# Active_comm_control_1_0.net
KiCad netlist of a schematic drawn in EAGLE
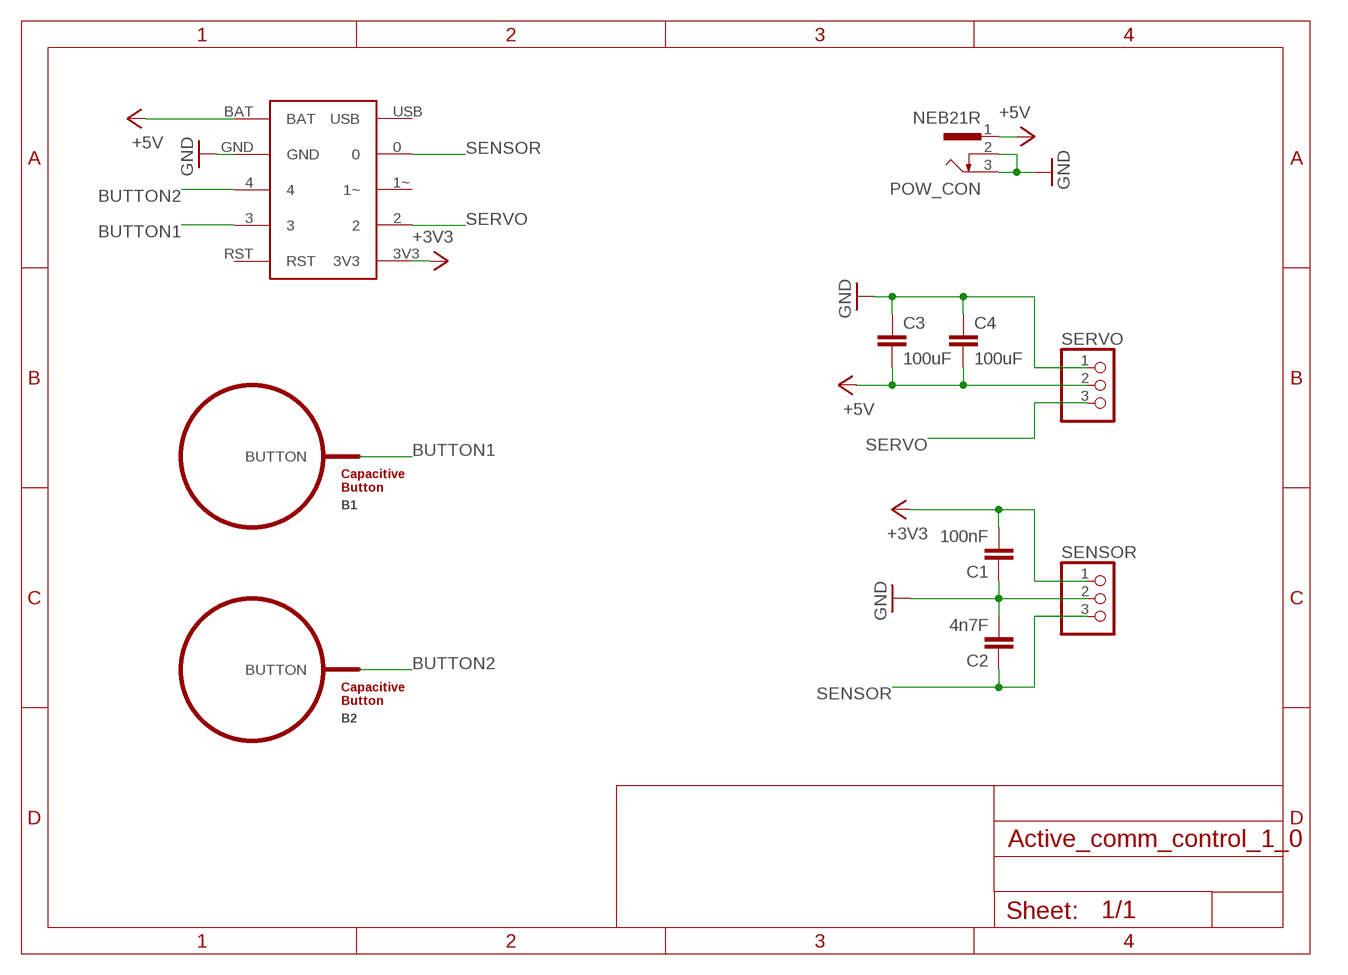
[diagram p0: schematic, sheet 1]

(export (version "E")
  (design (tool "Eeschema 10.0.6"))
  (components
    (comp (ref "B1")
      (value "BUTTON_PASSIVE10MM")
      (footprint "eagle-import:BUTTON_PASSIVE_10MM")
      (libsource (lib "eagle-import") (part "BUTTON_PASSIVE10MM"))
    )
    (comp (ref "B2")
      (value "BUTTON_PASSIVE10MM")
      (footprint "eagle-import:BUTTON_PASSIVE_10MM")
      (libsource (lib "eagle-import") (part "BUTTON_PASSIVE10MM"))
    )
    (comp (ref "C1")
      (value "100nF")
      (footprint "eagle-import:C0805")
      (libsource (lib "eagle-import") (part "resistor_C-EUC0805"))
    )
    (comp (ref "C2")
      (value "4n7F")
      (footprint "eagle-import:C0805")
      (libsource (lib "eagle-import") (part "resistor_C-EUC0805"))
    )
    (comp (ref "C3")
      (value "100uF")
      (footprint "eagle-import:C1206")
      (libsource (lib "eagle-import") (part "C-EUC1206"))
    )
    (comp (ref "C4")
      (value "100uF")
      (footprint "eagle-import:C1206")
      (libsource (lib "eagle-import") (part "C-EUC1206"))
    )
    (comp (ref "POW_CON")
      (value "NEB21R")
      (footprint "eagle-import:NEB21R")
      (fields (field (name "MPN") "NEB 21 R"))
      (libsource (lib "eagle-import") (part "NEB21R"))
    )
    (comp (ref "SENSOR")
      (value "PINHD-1X3")
      (footprint "eagle-import:1X03")
      (libsource (lib "eagle-import") (part "PINHD-1X3"))
    )
    (comp (ref "SERVO")
      (value "PINHD-1X3")
      (footprint "eagle-import:1X03")
      (libsource (lib "eagle-import") (part "PINHD-1X3"))
    )
    (comp (ref "TRINKET-M0")
      (value "TRINKET-M0")
      (footprint "eagle-import:TRINKET-M0-NO-HOLES")
      (libsource (lib "eagle-import") (part "TRINKET-M0"))
    )
  )
  (nets
    (net (code "1") (name "+3V3") (class "Default")
      (node (ref "C1") (pin "2") (pinfunction "2_2") (pintype "passive"))
      (node (ref "SENSOR") (pin "1") (pinfunction "1_1") (pintype "passive"))
      (node (ref "TRINKET-M0") (pin "3V3") (pinfunction "3V3_3V3") (pintype "bidirectional"))
    )
    (net (code "2") (name "+5V") (class "Default")
      (node (ref "C3") (pin "2") (pinfunction "2_2") (pintype "passive"))
      (node (ref "C4") (pin "2") (pinfunction "2_2") (pintype "passive"))
      (node (ref "POW_CON") (pin "1") (pinfunction "1_1") (pintype "passive"))
      (node (ref "SERVO") (pin "2") (pinfunction "2_2") (pintype "passive"))
      (node (ref "TRINKET-M0") (pin "BAT") (pinfunction "BAT_BAT") (pintype "bidirectional"))
    )
    (net (code "3") (name "/BUTTON1") (class "Default")
      (node (ref "B1") (pin "BUTTON") (pinfunction "BUTTON_BUTTON") (pintype "passive"))
      (node (ref "TRINKET-M0") (pin "3") (pinfunction "3_3") (pintype "bidirectional"))
    )
    (net (code "4") (name "/BUTTON2") (class "Default")
      (node (ref "B2") (pin "BUTTON") (pinfunction "BUTTON_BUTTON") (pintype "passive"))
      (node (ref "TRINKET-M0") (pin "4") (pinfunction "4_4") (pintype "bidirectional"))
    )
    (net (code "5") (name "/SENSOR") (class "Default")
      (node (ref "C2") (pin "1") (pinfunction "1_1") (pintype "passive"))
      (node (ref "SENSOR") (pin "3") (pinfunction "3_3") (pintype "passive"))
      (node (ref "TRINKET-M0") (pin "0") (pinfunction "0_0") (pintype "bidirectional"))
    )
    (net (code "6") (name "/SERVO") (class "Default")
      (node (ref "SERVO") (pin "3") (pinfunction "3_3") (pintype "passive"))
      (node (ref "TRINKET-M0") (pin "2") (pinfunction "2_2") (pintype "bidirectional"))
    )
    (net (code "7") (name "GND") (class "Default")
      (node (ref "C1") (pin "1") (pinfunction "1_1") (pintype "passive"))
      (node (ref "C2") (pin "2") (pinfunction "2_2") (pintype "passive"))
      (node (ref "C3") (pin "1") (pinfunction "1_1") (pintype "passive"))
      (node (ref "C4") (pin "1") (pinfunction "1_1") (pintype "passive"))
      (node (ref "POW_CON") (pin "2") (pinfunction "2_2") (pintype "passive"))
      (node (ref "POW_CON") (pin "3") (pinfunction "3_3") (pintype "passive"))
      (node (ref "SENSOR") (pin "2") (pinfunction "2_2") (pintype "passive"))
      (node (ref "SERVO") (pin "1") (pinfunction "1_1") (pintype "passive"))
      (node (ref "TRINKET-M0") (pin "GND") (pinfunction "GND_GND") (pintype "bidirectional"))
    )
    (net (code "8") (name "unconnected-(TRINKET-M0-1~{}-Pad1~)") (class "Default")
      (node (ref "TRINKET-M0") (pin "1~") (pinfunction "1~{}_1~") (pintype "bidirectional"))
    )
    (net (code "9") (name "unconnected-(TRINKET-M0-PadRST)") (class "Default")
      (node (ref "TRINKET-M0") (pin "RST") (pinfunction "RST_RST") (pintype "bidirectional"))
    )
    (net (code "10") (name "unconnected-(TRINKET-M0-PadUSB)") (class "Default")
      (node (ref "TRINKET-M0") (pin "USB") (pinfunction "USB_USB") (pintype "bidirectional"))
    )
  )
)
